# AquaNode_Model_A.net
KiCad netlist of a schematic drawn in EAGLE
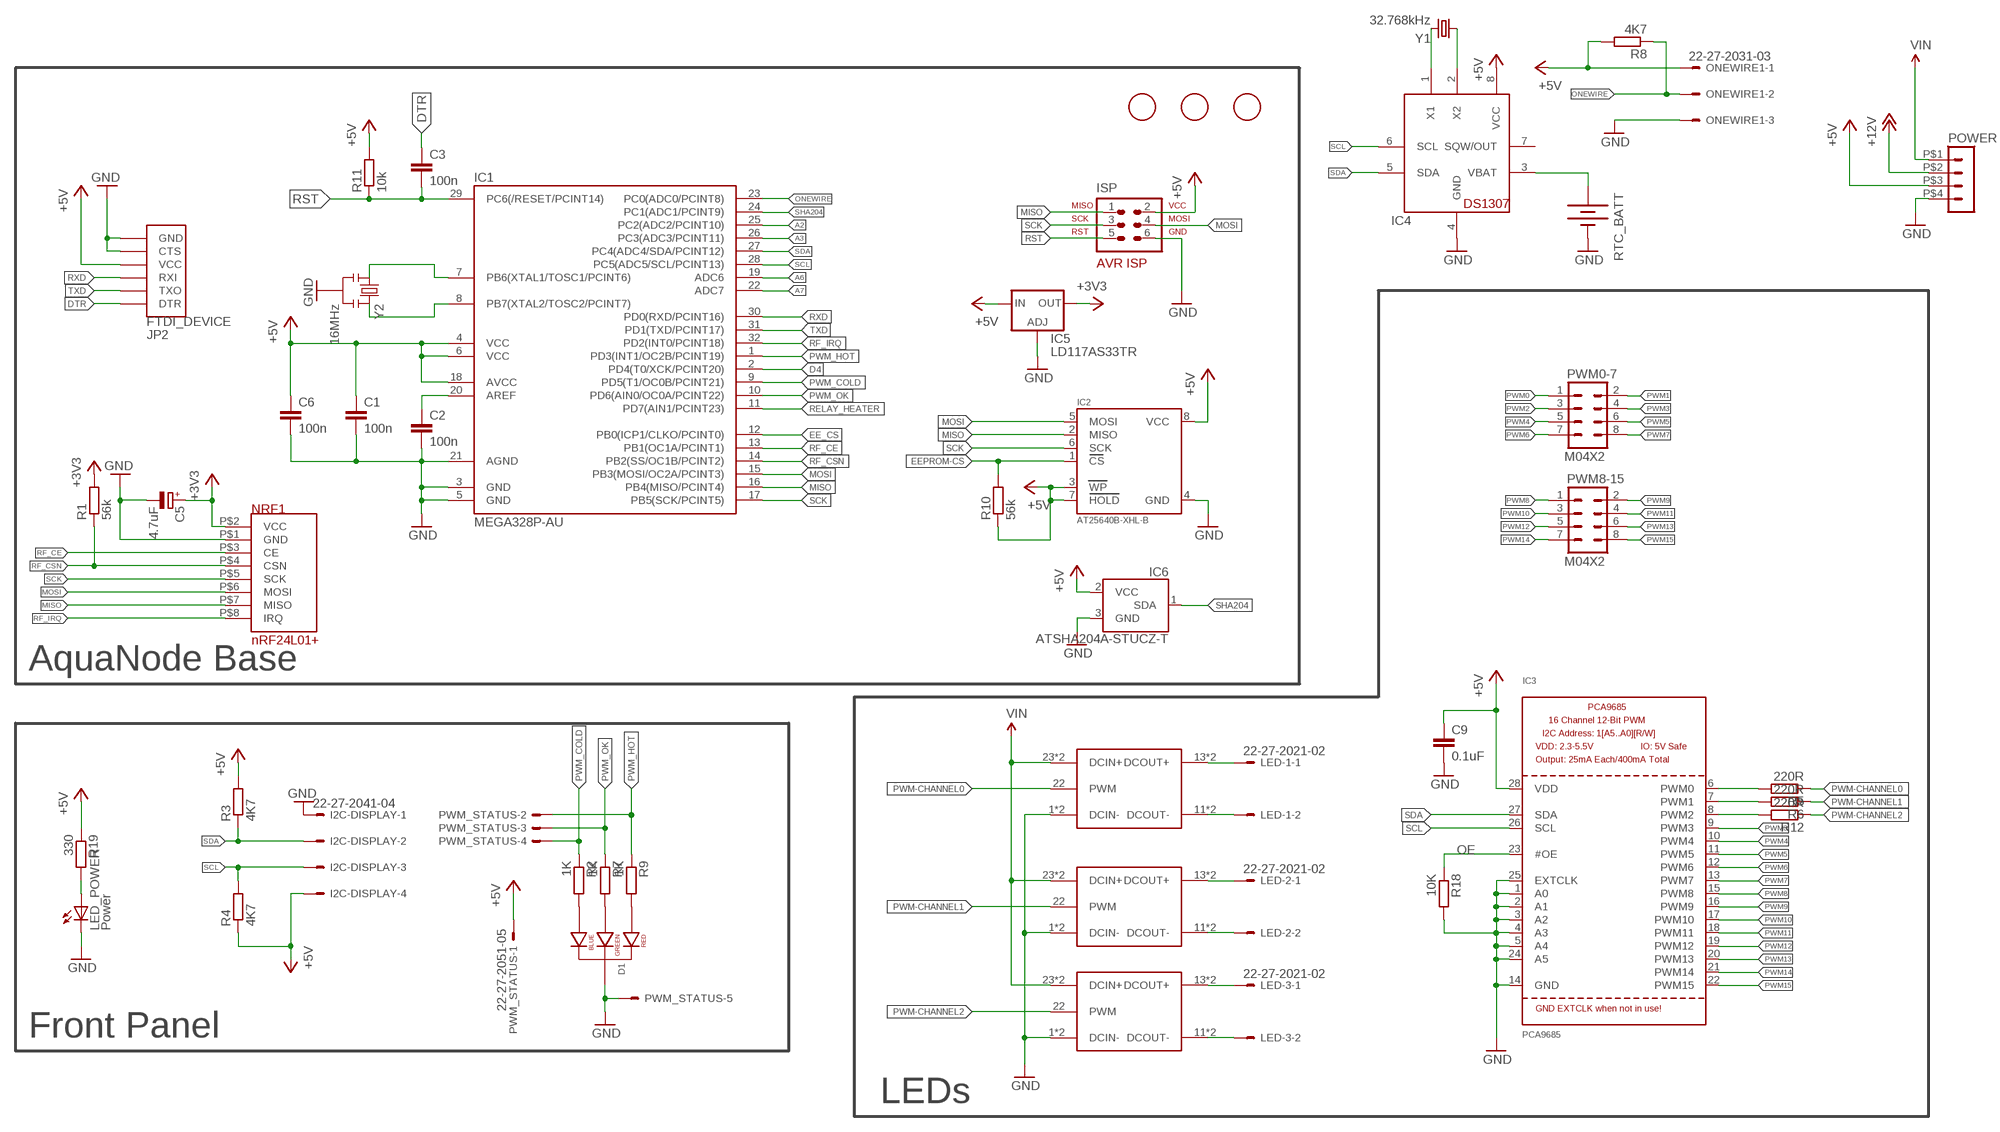
[diagram p0: schematic, sheet 1]

(export (version "E")
  (design (tool "Eeschema 10.0.6"))
  (components
    (comp (ref "C1")
      (value "100n")
      (footprint "eagle-import:C0603")
      (libsource (lib "eagle-import") (part "C-EUC0603"))
    )
    (comp (ref "C2")
      (value "100n")
      (footprint "eagle-import:C0603")
      (libsource (lib "eagle-import") (part "C-EUC0603"))
    )
    (comp (ref "C3")
      (value "100n")
      (footprint "eagle-import:C0603")
      (libsource (lib "eagle-import") (part "C-EUC0603"))
    )
    (comp (ref "C5")
      (value "4.7uF")
      (footprint "eagle-import:E2,5-6")
      (libsource (lib "eagle-import") (part "CPOL-EUE2.5-6"))
    )
    (comp (ref "C6")
      (value "100n")
      (footprint "eagle-import:C0603")
      (libsource (lib "eagle-import") (part "C-EUC0603"))
    )
    (comp (ref "C9")
      (value "0.1uF")
      (footprint "eagle-import:C0805")
      (libsource (lib "eagle-import") (part "C-EUC0805"))
    )
    (comp (ref "D1")
      (value "LED-RGB-CC")
      (footprint "eagle-import:LED-RGB-THRU")
      (libsource (lib "eagle-import") (part "LED-RGB-CC-THRUDIFFUSE"))
    )
    (comp (ref "DRV1")
      (value "DLL-XXXH")
      (footprint "eagle-import:LDD_H")
      (libsource (lib "eagle-import") (part "LDD_H"))
    )
    (comp (ref "DRV2")
      (value "DLL-XXXH")
      (footprint "eagle-import:LDD_H")
      (libsource (lib "eagle-import") (part "LDD_H"))
    )
    (comp (ref "DRV3")
      (value "DLL-XXXH")
      (footprint "eagle-import:LDD_H")
      (libsource (lib "eagle-import") (part "LDD_H"))
    )
    (comp (ref "FID1")
      (value "FIDUCIAL")
      (footprint "eagle-import:FIDUCIAL_1MM")
      (libsource (lib "eagle-import") (part "FIDUCIAL"))
    )
    (comp (ref "FID2")
      (value "FIDUCIAL")
      (footprint "eagle-import:FIDUCIAL_1MM")
      (libsource (lib "eagle-import") (part "FIDUCIAL"))
    )
    (comp (ref "FID3")
      (value "FIDUCIAL")
      (footprint "eagle-import:FIDUCIAL_1MM")
      (libsource (lib "eagle-import") (part "FIDUCIAL"))
    )
    (comp (ref "I2C-DISPLAY")
      (value "22-27-2041-04")
      (footprint "eagle-import:6410-04")
      (libsource (lib "eagle-import") (part "22-?-0427-2041"))
    )
    (comp (ref "IC1")
      (value "MEGA328P-AU")
      (footprint "eagle-import:TQFP32-08")
      (libsource (lib "eagle-import") (part "MEGA48/88/168-AU"))
    )
    (comp (ref "IC2")
      (value "AT25640B-XHL-B")
      (footprint "eagle-import:TSSOP8-4.4MM")
      (libsource (lib "eagle-import") (part "EEPROM_SPI_AT25040ATSSOP"))
    )
    (comp (ref "IC3")
      (value "PCA9685")
      (footprint "eagle-import:TSSOP28")
      (libsource (lib "eagle-import") (part "PCA9685"))
    )
    (comp (ref "IC4")
      (value "DS1307")
      (footprint "eagle-import:SO08")
      (libsource (lib "eagle-import") (part "DS1307SO08"))
    )
    (comp (ref "IC5")
      (value "LD117AS33TR")
      (footprint "eagle-import:SOT223")
      (libsource (lib "eagle-import") (part "LD117A?S33TR"))
    )
    (comp (ref "IC6")
      (value "ATSHA204A-STUCZ-T")
      (footprint "eagle-import:SOT23-3")
      (libsource (lib "eagle-import") (part "ATSHA204-TSU"))
    )
    (comp (ref "ISP")
      (value "ISP")
      (footprint "eagle-import:AVR-ISP-6")
      (libsource (lib "eagle-import") (part "AVR-ISP-6VERT"))
    )
    (comp (ref "JP2")
      (value "FTDI_DEVICE")
      (footprint "eagle-import:FTDI_DEVICE_SIDE")
      (libsource (lib "eagle-import") (part "FTDI_DEVICE"))
    )
    (comp (ref "LED-1")
      (value "22-27-2021-02")
      (footprint "eagle-import:6410-02")
      (libsource (lib "eagle-import") (part "22-?-0227-2021"))
    )
    (comp (ref "LED-2")
      (value "22-27-2021-02")
      (footprint "eagle-import:6410-02")
      (libsource (lib "eagle-import") (part "22-?-0227-2021"))
    )
    (comp (ref "LED-3")
      (value "22-27-2021-02")
      (footprint "eagle-import:6410-02")
      (libsource (lib "eagle-import") (part "22-?-0227-2021"))
    )
    (comp (ref "LED_POWER")
      (value "Power")
      (footprint "eagle-import:LED3MM")
      (libsource (lib "eagle-import") (part "LED3MM"))
    )
    (comp (ref "NRF1")
      (value "NRF24L01+.EBAY")
      (footprint "eagle-import:NRF24L01+.EBAY")
      (libsource (lib "eagle-import") (part "NRF24L01+.EBAY"))
    )
    (comp (ref "ONEWIRE1")
      (value "22-27-2031-03")
      (footprint "eagle-import:6410-03")
      (libsource (lib "eagle-import") (part "22-?-0327-2031"))
    )
    (comp (ref "POWER")
      (value "HEADER_POS4_43045-0412")
      (footprint "eagle-import:43045-0412")
      (libsource (lib "eagle-import") (part "HEADER_POS4_?43045-0412"))
    )
    (comp (ref "PWM0-7")
      (value "M04X2")
      (footprint "eagle-import:2X4")
      (libsource (lib "eagle-import") (part "M04X2"))
    )
    (comp (ref "PWM8-15")
      (value "M04X2")
      (footprint "eagle-import:2X4")
      (libsource (lib "eagle-import") (part "M04X2"))
    )
    (comp (ref "PWM_STATUS")
      (value "22-27-2051-05")
      (footprint "eagle-import:6410-05")
      (libsource (lib "eagle-import") (part "22-?-0527-2051"))
    )
    (comp (ref "R1")
      (value "56k")
      (footprint "eagle-import:M0805")
      (libsource (lib "eagle-import") (part "R-EU_M0805"))
    )
    (comp (ref "R2")
      (value "1K")
      (footprint "eagle-import:M0805")
      (libsource (lib "eagle-import") (part "R-EU_M0805"))
    )
    (comp (ref "R3")
      (value "4K7")
      (footprint "eagle-import:M0805")
      (libsource (lib "eagle-import") (part "R-EU_M0805"))
    )
    (comp (ref "R4")
      (value "4K7")
      (footprint "eagle-import:M0805")
      (libsource (lib "eagle-import") (part "R-EU_M0805"))
    )
    (comp (ref "R5")
      (value "220R")
      (footprint "eagle-import:M0805")
      (libsource (lib "eagle-import") (part "R-EU_M0805"))
    )
    (comp (ref "R6")
      (value "220R")
      (footprint "eagle-import:M0805")
      (libsource (lib "eagle-import") (part "R-EU_M0805"))
    )
    (comp (ref "R7")
      (value "1K")
      (footprint "eagle-import:M0805")
      (libsource (lib "eagle-import") (part "R-EU_M0805"))
    )
    (comp (ref "R8")
      (value "4K7")
      (footprint "eagle-import:M0805")
      (libsource (lib "eagle-import") (part "R-EU_M0805"))
    )
    (comp (ref "R9")
      (value "1K")
      (footprint "eagle-import:M0805")
      (libsource (lib "eagle-import") (part "R-EU_M0805"))
    )
    (comp (ref "R10")
      (value "56k")
      (footprint "eagle-import:M0805")
      (libsource (lib "eagle-import") (part "R-EU_M0805"))
    )
    (comp (ref "R11")
      (value "10k")
      (footprint "eagle-import:R0603")
      (libsource (lib "eagle-import") (part "R-EU_R0603"))
    )
    (comp (ref "R12")
      (value "220R")
      (footprint "eagle-import:M0805")
      (libsource (lib "eagle-import") (part "R-EU_M0805"))
    )
    (comp (ref "R18")
      (value "10K")
      (footprint "eagle-import:M0805")
      (libsource (lib "eagle-import") (part "R-EU_M0805"))
    )
    (comp (ref "R19")
      (value "330")
      (footprint "eagle-import:M0805")
      (libsource (lib "eagle-import") (part "R-EU_M0805"))
    )
    (comp (ref "RTC_BATT")
      (value "BATTERY20SMD")
      (footprint "eagle-import:BATTCON_20MM")
      (libsource (lib "eagle-import") (part "BATTERY20SMD"))
    )
    (comp (ref "Y1")
      (value "32.768kHz")
      (footprint "eagle-import:CRYSTAL-32KHZ-SMD")
      (libsource (lib "eagle-import") (part "CRYSTAL32-SMD"))
    )
    (comp (ref "Y2")
      (value "16MHz")
      (footprint "eagle-import:RESONATOR-PTH")
      (libsource (lib "eagle-import") (part "RESONATORPTH"))
    )
  )
  (nets
    (net (code "1") (name "+3V3") (class "Default")
      (node (ref "C5") (pin "+") (pinfunction "+_+") (pintype "passive"))
      (node (ref "IC5") (pin "4") (pinfunction "OUT_4") (pintype "passive"))
      (node (ref "NRF1") (pin "P$2") (pinfunction "VCC_P$2") (pintype "power_in"))
      (node (ref "R1") (pin "2") (pinfunction "2_2") (pintype "passive"))
    )
    (net (code "2") (name "+5V") (class "Default")
      (node (ref "C1") (pin "1") (pinfunction "1_1") (pintype "passive"))
      (node (ref "C6") (pin "1") (pinfunction "1_1") (pintype "passive"))
      (node (ref "C9") (pin "1") (pinfunction "1_1") (pintype "passive"))
      (node (ref "I2C-DISPLAY") (pin "4") (pinfunction "S_4") (pintype "passive"))
      (node (ref "IC1") (pin "18") (pinfunction "AVCC_18") (pintype "passive"))
      (node (ref "IC1") (pin "4") (pinfunction "VCC_4") (pintype "power_in"))
      (node (ref "IC1") (pin "6") (pinfunction "VCC_6") (pintype "power_in"))
      (node (ref "IC2") (pin "3") (pinfunction "WP_3") (pintype "bidirectional"))
      (node (ref "IC2") (pin "7") (pinfunction "HOLD_7") (pintype "bidirectional"))
      (node (ref "IC2") (pin "8") (pinfunction "VCC_8") (pintype "power_in"))
      (node (ref "IC3") (pin "28") (pinfunction "VDD_28") (pintype "power_in"))
      (node (ref "IC4") (pin "8") (pinfunction "VCC_8") (pintype "power_in"))
      (node (ref "IC5") (pin "3") (pinfunction "IN_3") (pintype "input"))
      (node (ref "IC6") (pin "2") (pinfunction "VCC_2") (pintype "bidirectional"))
      (node (ref "ISP") (pin "2") (pinfunction "2_2") (pintype "passive"))
      (node (ref "JP2") (pin "P$4") (pinfunction "VCC_P$4") (pintype "bidirectional"))
      (node (ref "ONEWIRE1") (pin "1") (pinfunction "S_1") (pintype "passive"))
      (node (ref "POWER") (pin "P$3") (pinfunction "3_P$3") (pintype "passive"))
      (node (ref "PWM_STATUS") (pin "1") (pinfunction "S_1") (pintype "passive"))
      (node (ref "R10") (pin "1") (pinfunction "1_1") (pintype "passive"))
      (node (ref "R11") (pin "2") (pinfunction "2_2") (pintype "passive"))
      (node (ref "R19") (pin "1") (pinfunction "1_1") (pintype "passive"))
      (node (ref "R3") (pin "2") (pinfunction "2_2") (pintype "passive"))
      (node (ref "R4") (pin "1") (pinfunction "1_1") (pintype "passive"))
      (node (ref "R8") (pin "2") (pinfunction "2_2") (pintype "passive"))
    )
    (net (code "3") (name "+12V") (class "Default")
      (node (ref "POWER") (pin "P$2") (pinfunction "2_P$2") (pintype "passive"))
    )
    (net (code "4") (name "/OE") (class "Default")
      (node (ref "IC3") (pin "23") (pinfunction "#OE_23") (pintype "input"))
      (node (ref "R18") (pin "1") (pinfunction "1_1") (pintype "passive"))
    )
    (net (code "5") (name "A2") (class "Default")
      (node (ref "IC1") (pin "25") (pinfunction "PC2(ADC2/PCINT10)_25") (pintype "bidirectional"))
    )
    (net (code "6") (name "A3") (class "Default")
      (node (ref "IC1") (pin "26") (pinfunction "PC3(ADC3/PCINT11)_26") (pintype "bidirectional"))
    )
    (net (code "7") (name "A6") (class "Default")
      (node (ref "IC1") (pin "19") (pinfunction "ADC6_19") (pintype "passive"))
    )
    (net (code "8") (name "A7") (class "Default")
      (node (ref "IC1") (pin "22") (pinfunction "ADC7_22") (pintype "passive"))
    )
    (net (code "9") (name "D4") (class "Default")
      (node (ref "IC1") (pin "2") (pinfunction "PD4(T0/XCK/PCINT20)_2") (pintype "bidirectional"))
    )
    (net (code "10") (name "DTR") (class "Default")
      (node (ref "C3") (pin "1") (pinfunction "1_1") (pintype "passive"))
      (node (ref "JP2") (pin "P$1") (pinfunction "DTR_P$1") (pintype "bidirectional"))
    )
    (net (code "11") (name "EEPROM-CS") (class "Default")
      (node (ref "IC2") (pin "1") (pinfunction "CS_1") (pintype "bidirectional"))
      (node (ref "R10") (pin "2") (pinfunction "2_2") (pintype "passive"))
    )
    (net (code "12") (name "EE_CS") (class "Default")
      (node (ref "IC1") (pin "12") (pinfunction "PB0(ICP1/CLKO/PCINT0)_12") (pintype "bidirectional"))
    )
    (net (code "13") (name "GND") (class "Default")
      (node (ref "C1") (pin "2") (pinfunction "2_2") (pintype "passive"))
      (node (ref "C2") (pin "2") (pinfunction "2_2") (pintype "passive"))
      (node (ref "C5") (pin "-") (pinfunction "-_-") (pintype "passive"))
      (node (ref "C6") (pin "2") (pinfunction "2_2") (pintype "passive"))
      (node (ref "C9") (pin "2") (pinfunction "2_2") (pintype "passive"))
      (node (ref "D1") (pin "2") (pinfunction "CATHODE_2") (pintype "bidirectional"))
      (node (ref "DRV1") (pin "1") (pinfunction "DCIN-_1") (pintype "input"))
      (node (ref "DRV1") (pin "2") (pinfunction "DCIN-_2") (pintype "input"))
      (node (ref "DRV2") (pin "1") (pinfunction "DCIN-_1") (pintype "input"))
      (node (ref "DRV2") (pin "2") (pinfunction "DCIN-_2") (pintype "input"))
      (node (ref "DRV3") (pin "1") (pinfunction "DCIN-_1") (pintype "input"))
      (node (ref "DRV3") (pin "2") (pinfunction "DCIN-_2") (pintype "input"))
      (node (ref "I2C-DISPLAY") (pin "1") (pinfunction "S_1") (pintype "passive"))
      (node (ref "IC1") (pin "21") (pinfunction "AGND_21") (pintype "power_in"))
      (node (ref "IC1") (pin "3") (pinfunction "GND_3") (pintype "power_in"))
      (node (ref "IC1") (pin "5") (pinfunction "GND_5") (pintype "power_in"))
      (node (ref "IC2") (pin "4") (pinfunction "GND_4") (pintype "power_in"))
      (node (ref "IC3") (pin "1") (pinfunction "A0_1") (pintype "bidirectional"))
      (node (ref "IC3") (pin "14") (pinfunction "GND_14") (pintype "power_in"))
      (node (ref "IC3") (pin "2") (pinfunction "A1_2") (pintype "bidirectional"))
      (node (ref "IC3") (pin "24") (pinfunction "A5_24") (pintype "bidirectional"))
      (node (ref "IC3") (pin "25") (pinfunction "EXTCLK_25") (pintype "input"))
      (node (ref "IC3") (pin "3") (pinfunction "A2_3") (pintype "bidirectional"))
      (node (ref "IC3") (pin "4") (pinfunction "A3_4") (pintype "bidirectional"))
      (node (ref "IC3") (pin "5") (pinfunction "A4_5") (pintype "bidirectional"))
      (node (ref "IC4") (pin "4") (pinfunction "GND_4") (pintype "power_in"))
      (node (ref "IC5") (pin "1") (pinfunction "ADJ_1") (pintype "input"))
      (node (ref "IC6") (pin "3") (pinfunction "GND_3") (pintype "bidirectional"))
      (node (ref "ISP") (pin "6") (pinfunction "6_6") (pintype "passive"))
      (node (ref "JP2") (pin "P$5") (pinfunction "CTS_P$5") (pintype "bidirectional"))
      (node (ref "JP2") (pin "P$6") (pinfunction "GND_P$6") (pintype "bidirectional"))
      (node (ref "LED_POWER") (pin "K") (pinfunction "C_K") (pintype "passive"))
      (node (ref "NRF1") (pin "P$1") (pinfunction "GND_P$1") (pintype "power_in"))
      (node (ref "ONEWIRE1") (pin "3") (pinfunction "S_3") (pintype "passive"))
      (node (ref "POWER") (pin "P$4") (pinfunction "4_P$4") (pintype "passive"))
      (node (ref "PWM_STATUS") (pin "5") (pinfunction "S_5") (pintype "passive"))
      (node (ref "R18") (pin "2") (pinfunction "2_2") (pintype "passive"))
      (node (ref "RTC_BATT") (pin "2") (pinfunction "-_2") (pintype "power_in"))
      (node (ref "Y2") (pin "2") (pinfunction "2_2") (pintype "passive"))
    )
    (net (code "14") (name "MISO") (class "Default")
      (node (ref "IC1") (pin "16") (pinfunction "PB4(MISO/PCINT4)_16") (pintype "bidirectional"))
      (node (ref "IC2") (pin "2") (pinfunction "MISO_2") (pintype "bidirectional"))
      (node (ref "ISP") (pin "1") (pinfunction "1_1") (pintype "passive"))
      (node (ref "NRF1") (pin "P$7") (pinfunction "MISO_P$7") (pintype "bidirectional"))
    )
    (net (code "15") (name "MOSI") (class "Default")
      (node (ref "IC1") (pin "15") (pinfunction "PB3(MOSI/OC2A/PCINT3)_15") (pintype "bidirectional"))
      (node (ref "IC2") (pin "5") (pinfunction "MOSI_5") (pintype "bidirectional"))
      (node (ref "ISP") (pin "4") (pinfunction "4_4") (pintype "passive"))
      (node (ref "NRF1") (pin "P$6") (pinfunction "MOSI_P$6") (pintype "bidirectional"))
    )
    (net (code "16") (name "Net-(D1-BLUE_CATHODE)") (class "Default")
      (node (ref "D1") (pin "4") (pinfunction "BLUE_CATHODE_4") (pintype "bidirectional"))
      (node (ref "R2") (pin "2") (pinfunction "2_2") (pintype "passive"))
    )
    (net (code "17") (name "Net-(D1-GREEN_CATHODE)") (class "Default")
      (node (ref "D1") (pin "3") (pinfunction "GREEN_CATHODE_3") (pintype "bidirectional"))
      (node (ref "R7") (pin "2") (pinfunction "2_2") (pintype "passive"))
    )
    (net (code "18") (name "Net-(D1-RED_CATHODE)") (class "Default")
      (node (ref "D1") (pin "1") (pinfunction "RED_CATHODE_1") (pintype "bidirectional"))
      (node (ref "R9") (pin "2") (pinfunction "2_2") (pintype "passive"))
    )
    (net (code "19") (name "Net-(IC1-AREF)") (class "Default")
      (node (ref "C2") (pin "1") (pinfunction "1_1") (pintype "passive"))
      (node (ref "IC1") (pin "20") (pinfunction "AREF_20") (pintype "passive"))
    )
    (net (code "20") (name "Net-(IC1-PB6(XTAL1{slash}TOSC1{slash}PCINT6))") (class "Default")
      (node (ref "IC1") (pin "7") (pinfunction "PB6(XTAL1/TOSC1/PCINT6)_7") (pintype "bidirectional"))
      (node (ref "Y2") (pin "1") (pinfunction "1_1") (pintype "passive"))
    )
    (net (code "21") (name "Net-(IC1-PB7(XTAL2{slash}TOSC2{slash}PCINT7))") (class "Default")
      (node (ref "IC1") (pin "8") (pinfunction "PB7(XTAL2/TOSC2/PCINT7)_8") (pintype "bidirectional"))
      (node (ref "Y2") (pin "3") (pinfunction "3_3") (pintype "passive"))
    )
    (net (code "22") (name "Net-(IC4-VBAT)") (class "Default")
      (node (ref "IC4") (pin "3") (pinfunction "VBAT_3") (pintype "power_in"))
      (node (ref "RTC_BATT") (pin "1") (pinfunction "+_1") (pintype "power_in"))
    )
    (net (code "23") (name "Net-(IC4-X1)") (class "Default")
      (node (ref "IC4") (pin "1") (pinfunction "X1_1") (pintype "passive"))
      (node (ref "Y1") (pin "X2") (pinfunction "2_X2") (pintype "passive"))
    )
    (net (code "24") (name "Net-(IC4-X2)") (class "Default")
      (node (ref "IC4") (pin "2") (pinfunction "X2_2") (pintype "passive"))
      (node (ref "Y1") (pin "X1") (pinfunction "1_X1") (pintype "passive"))
    )
    (net (code "25") (name "Net-(LED-1A-S)") (class "Default")
      (node (ref "DRV1") (pin "13") (pinfunction "DCOUT+_13") (pintype "output"))
      (node (ref "DRV1") (pin "14") (pinfunction "DCOUT+_14") (pintype "output"))
      (node (ref "LED-1") (pin "1") (pinfunction "S_1") (pintype "passive"))
    )
    (net (code "26") (name "Net-(LED-1B-S)") (class "Default")
      (node (ref "DRV1") (pin "11") (pinfunction "DCOUT-_11") (pintype "output"))
      (node (ref "DRV1") (pin "12") (pinfunction "DCOUT-_12") (pintype "output"))
      (node (ref "LED-1") (pin "2") (pinfunction "S_2") (pintype "passive"))
    )
    (net (code "27") (name "Net-(LED-2A-S)") (class "Default")
      (node (ref "DRV2") (pin "13") (pinfunction "DCOUT+_13") (pintype "output"))
      (node (ref "DRV2") (pin "14") (pinfunction "DCOUT+_14") (pintype "output"))
      (node (ref "LED-2") (pin "1") (pinfunction "S_1") (pintype "passive"))
    )
    (net (code "28") (name "Net-(LED-2B-S)") (class "Default")
      (node (ref "DRV2") (pin "11") (pinfunction "DCOUT-_11") (pintype "output"))
      (node (ref "DRV2") (pin "12") (pinfunction "DCOUT-_12") (pintype "output"))
      (node (ref "LED-2") (pin "2") (pinfunction "S_2") (pintype "passive"))
    )
    (net (code "29") (name "Net-(LED-3A-S)") (class "Default")
      (node (ref "DRV3") (pin "13") (pinfunction "DCOUT+_13") (pintype "output"))
      (node (ref "DRV3") (pin "14") (pinfunction "DCOUT+_14") (pintype "output"))
      (node (ref "LED-3") (pin "1") (pinfunction "S_1") (pintype "passive"))
    )
    (net (code "30") (name "Net-(LED-3B-S)") (class "Default")
      (node (ref "DRV3") (pin "11") (pinfunction "DCOUT-_11") (pintype "output"))
      (node (ref "DRV3") (pin "12") (pinfunction "DCOUT-_12") (pintype "output"))
      (node (ref "LED-3") (pin "2") (pinfunction "S_2") (pintype "passive"))
    )
    (net (code "31") (name "Net-(LED_POWER-PadA)") (class "Default")
      (node (ref "LED_POWER") (pin "A") (pinfunction "A_A") (pintype "passive"))
      (node (ref "R19") (pin "2") (pinfunction "2_2") (pintype "passive"))
    )
    (net (code "32") (name "ONEWIRE") (class "Default")
      (node (ref "IC1") (pin "23") (pinfunction "PC0(ADC0/PCINT8)_23") (pintype "bidirectional"))
      (node (ref "ONEWIRE1") (pin "2") (pinfunction "S_2") (pintype "passive"))
      (node (ref "R8") (pin "1") (pinfunction "1_1") (pintype "passive"))
    )
    (net (code "33") (name "PWM-CHANNEL0") (class "Default")
      (node (ref "DRV1") (pin "22") (pinfunction "PWM_22") (pintype "bidirectional"))
      (node (ref "R5") (pin "1") (pinfunction "1_1") (pintype "passive"))
    )
    (net (code "34") (name "PWM-CHANNEL1") (class "Default")
      (node (ref "DRV2") (pin "22") (pinfunction "PWM_22") (pintype "bidirectional"))
      (node (ref "R6") (pin "1") (pinfunction "1_1") (pintype "passive"))
    )
    (net (code "35") (name "PWM-CHANNEL2") (class "Default")
      (node (ref "DRV3") (pin "22") (pinfunction "PWM_22") (pintype "bidirectional"))
      (node (ref "R12") (pin "1") (pinfunction "1_1") (pintype "passive"))
    )
    (net (code "36") (name "PWM0") (class "Default")
      (node (ref "IC3") (pin "6") (pinfunction "PWM0_6") (pintype "output"))
      (node (ref "PWM0-7") (pin "1") (pinfunction "1_1") (pintype "passive"))
      (node (ref "R5") (pin "2") (pinfunction "2_2") (pintype "passive"))
    )
    (net (code "37") (name "PWM1") (class "Default")
      (node (ref "IC3") (pin "7") (pinfunction "PWM1_7") (pintype "output"))
      (node (ref "PWM0-7") (pin "2") (pinfunction "2_2") (pintype "passive"))
      (node (ref "R6") (pin "2") (pinfunction "2_2") (pintype "passive"))
    )
    (net (code "38") (name "PWM2") (class "Default")
      (node (ref "IC3") (pin "8") (pinfunction "PWM2_8") (pintype "output"))
      (node (ref "PWM0-7") (pin "3") (pinfunction "3_3") (pintype "passive"))
      (node (ref "R12") (pin "2") (pinfunction "2_2") (pintype "passive"))
    )
    (net (code "39") (name "PWM3") (class "Default")
      (node (ref "IC3") (pin "9") (pinfunction "PWM3_9") (pintype "output"))
      (node (ref "PWM0-7") (pin "4") (pinfunction "4_4") (pintype "passive"))
    )
    (net (code "40") (name "PWM4") (class "Default")
      (node (ref "IC3") (pin "10") (pinfunction "PWM4_10") (pintype "output"))
      (node (ref "PWM0-7") (pin "5") (pinfunction "5_5") (pintype "passive"))
    )
    (net (code "41") (name "PWM5") (class "Default")
      (node (ref "IC3") (pin "11") (pinfunction "PWM5_11") (pintype "output"))
      (node (ref "PWM0-7") (pin "6") (pinfunction "6_6") (pintype "passive"))
    )
    (net (code "42") (name "PWM6") (class "Default")
      (node (ref "IC3") (pin "12") (pinfunction "PWM6_12") (pintype "output"))
      (node (ref "PWM0-7") (pin "7") (pinfunction "7_7") (pintype "passive"))
    )
    (net (code "43") (name "PWM7") (class "Default")
      (node (ref "IC3") (pin "13") (pinfunction "PWM7_13") (pintype "output"))
      (node (ref "PWM0-7") (pin "8") (pinfunction "8_8") (pintype "passive"))
    )
    (net (code "44") (name "PWM8") (class "Default")
      (node (ref "IC3") (pin "15") (pinfunction "PWM8_15") (pintype "output"))
      (node (ref "PWM8-15") (pin "1") (pinfunction "1_1") (pintype "passive"))
    )
    (net (code "45") (name "PWM9") (class "Default")
      (node (ref "IC3") (pin "16") (pinfunction "PWM9_16") (pintype "output"))
      (node (ref "PWM8-15") (pin "2") (pinfunction "2_2") (pintype "passive"))
    )
    (net (code "46") (name "PWM10") (class "Default")
      (node (ref "IC3") (pin "17") (pinfunction "PWM10_17") (pintype "output"))
      (node (ref "PWM8-15") (pin "3") (pinfunction "3_3") (pintype "passive"))
    )
    (net (code "47") (name "PWM11") (class "Default")
      (node (ref "IC3") (pin "18") (pinfunction "PWM11_18") (pintype "output"))
      (node (ref "PWM8-15") (pin "4") (pinfunction "4_4") (pintype "passive"))
    )
    (net (code "48") (name "PWM12") (class "Default")
      (node (ref "IC3") (pin "19") (pinfunction "PWM12_19") (pintype "output"))
      (node (ref "PWM8-15") (pin "5") (pinfunction "5_5") (pintype "passive"))
    )
    (net (code "49") (name "PWM13") (class "Default")
      (node (ref "IC3") (pin "20") (pinfunction "PWM13_20") (pintype "output"))
      (node (ref "PWM8-15") (pin "6") (pinfunction "6_6") (pintype "passive"))
    )
    (net (code "50") (name "PWM14") (class "Default")
      (node (ref "IC3") (pin "21") (pinfunction "PWM14_21") (pintype "output"))
      (node (ref "PWM8-15") (pin "7") (pinfunction "7_7") (pintype "passive"))
    )
    (net (code "51") (name "PWM15") (class "Default")
      (node (ref "IC3") (pin "22") (pinfunction "PWM15_22") (pintype "output"))
      (node (ref "PWM8-15") (pin "8") (pinfunction "8_8") (pintype "passive"))
    )
    (net (code "52") (name "PWM_COLD") (class "Default")
      (node (ref "IC1") (pin "9") (pinfunction "PD5(T1/OC0B/PCINT21)_9") (pintype "bidirectional"))
      (node (ref "PWM_STATUS") (pin "4") (pinfunction "S_4") (pintype "passive"))
      (node (ref "R2") (pin "1") (pinfunction "1_1") (pintype "passive"))
    )
    (net (code "53") (name "PWM_HOT") (class "Default")
      (node (ref "IC1") (pin "1") (pinfunction "PD3(INT1/OC2B/PCINT19)_1") (pintype "bidirectional"))
      (node (ref "PWM_STATUS") (pin "2") (pinfunction "S_2") (pintype "passive"))
      (node (ref "R9") (pin "1") (pinfunction "1_1") (pintype "passive"))
    )
    (net (code "54") (name "PWM_OK") (class "Default")
      (node (ref "IC1") (pin "10") (pinfunction "PD6(AIN0/OC0A/PCINT22)_10") (pintype "bidirectional"))
      (node (ref "PWM_STATUS") (pin "3") (pinfunction "S_3") (pintype "passive"))
      (node (ref "R7") (pin "1") (pinfunction "1_1") (pintype "passive"))
    )
    (net (code "55") (name "RELAY_HEATER") (class "Default")
      (node (ref "IC1") (pin "11") (pinfunction "PD7(AIN1/PCINT23)_11") (pintype "bidirectional"))
    )
    (net (code "56") (name "RF_CE") (class "Default")
      (node (ref "IC1") (pin "13") (pinfunction "PB1(OC1A/PCINT1)_13") (pintype "bidirectional"))
      (node (ref "NRF1") (pin "P$3") (pinfunction "CE_P$3") (pintype "bidirectional"))
    )
    (net (code "57") (name "RF_CSN") (class "Default")
      (node (ref "IC1") (pin "14") (pinfunction "PB2(SS/OC1B/PCINT2)_14") (pintype "bidirectional"))
      (node (ref "NRF1") (pin "P$4") (pinfunction "CSN_P$4") (pintype "bidirectional"))
      (node (ref "R1") (pin "1") (pinfunction "1_1") (pintype "passive"))
    )
    (net (code "58") (name "RF_IRQ") (class "Default")
      (node (ref "IC1") (pin "32") (pinfunction "PD2(INT0/PCINT18)_32") (pintype "bidirectional"))
      (node (ref "NRF1") (pin "P$8") (pinfunction "IRQ_P$8") (pintype "bidirectional"))
    )
    (net (code "59") (name "RST") (class "Default")
      (node (ref "C3") (pin "2") (pinfunction "2_2") (pintype "passive"))
      (node (ref "IC1") (pin "29") (pinfunction "PC6(/RESET/PCINT14)_29") (pintype "bidirectional"))
      (node (ref "ISP") (pin "5") (pinfunction "5_5") (pintype "passive"))
      (node (ref "R11") (pin "1") (pinfunction "1_1") (pintype "passive"))
    )
    (net (code "60") (name "RXD") (class "Default")
      (node (ref "IC1") (pin "30") (pinfunction "PD0(RXD/PCINT16)_30") (pintype "bidirectional"))
      (node (ref "JP2") (pin "P$3") (pinfunction "RXI_P$3") (pintype "bidirectional"))
    )
    (net (code "61") (name "SCK") (class "Default")
      (node (ref "IC1") (pin "17") (pinfunction "PB5(SCK/PCINT5)_17") (pintype "bidirectional"))
      (node (ref "IC2") (pin "6") (pinfunction "SCK_6") (pintype "bidirectional"))
      (node (ref "ISP") (pin "3") (pinfunction "3_3") (pintype "passive"))
      (node (ref "NRF1") (pin "P$5") (pinfunction "SCK_P$5") (pintype "bidirectional"))
    )
    (net (code "62") (name "SCL") (class "Default")
      (node (ref "I2C-DISPLAY") (pin "3") (pinfunction "S_3") (pintype "passive"))
      (node (ref "IC1") (pin "28") (pinfunction "PC5(ADC5/SCL/PCINT13)_28") (pintype "bidirectional"))
      (node (ref "IC3") (pin "26") (pinfunction "SCL_26") (pintype "bidirectional"))
      (node (ref "IC4") (pin "6") (pinfunction "SCL_6") (pintype "bidirectional"))
      (node (ref "R4") (pin "2") (pinfunction "2_2") (pintype "passive"))
    )
    (net (code "63") (name "SDA") (class "Default")
      (node (ref "I2C-DISPLAY") (pin "2") (pinfunction "S_2") (pintype "passive"))
      (node (ref "IC1") (pin "27") (pinfunction "PC4(ADC4/SDA/PCINT12)_27") (pintype "bidirectional"))
      (node (ref "IC3") (pin "27") (pinfunction "SDA_27") (pintype "bidirectional"))
      (node (ref "IC4") (pin "5") (pinfunction "SDA_5") (pintype "bidirectional"))
      (node (ref "R3") (pin "1") (pinfunction "1_1") (pintype "passive"))
    )
    (net (code "64") (name "SHA204") (class "Default")
      (node (ref "IC1") (pin "24") (pinfunction "PC1(ADC1/PCINT9)_24") (pintype "bidirectional"))
      (node (ref "IC6") (pin "1") (pinfunction "SDA_1") (pintype "bidirectional"))
    )
    (net (code "65") (name "TXD") (class "Default")
      (node (ref "IC1") (pin "31") (pinfunction "PD1(TXD/PCINT17)_31") (pintype "bidirectional"))
      (node (ref "JP2") (pin "P$2") (pinfunction "TXO_P$2") (pintype "bidirectional"))
    )
    (net (code "66") (name "VIN") (class "Default")
      (node (ref "DRV1") (pin "23") (pinfunction "DCIN+_23") (pintype "input"))
      (node (ref "DRV1") (pin "24") (pinfunction "DCIN+_24") (pintype "input"))
      (node (ref "DRV2") (pin "23") (pinfunction "DCIN+_23") (pintype "input"))
      (node (ref "DRV2") (pin "24") (pinfunction "DCIN+_24") (pintype "input"))
      (node (ref "DRV3") (pin "23") (pinfunction "DCIN+_23") (pintype "input"))
      (node (ref "DRV3") (pin "24") (pinfunction "DCIN+_24") (pintype "input"))
      (node (ref "POWER") (pin "P$1") (pinfunction "1_P$1") (pintype "passive"))
    )
    (net (code "67") (name "unconnected-(IC4-SQW{slash}OUT-Pad7)") (class "Default")
      (node (ref "IC4") (pin "7") (pinfunction "SQW/OUT_7") (pintype "bidirectional"))
    )
  )
)
